# 1A_MAIN.net
KiCad netlist of a schematic drawn in EAGLE
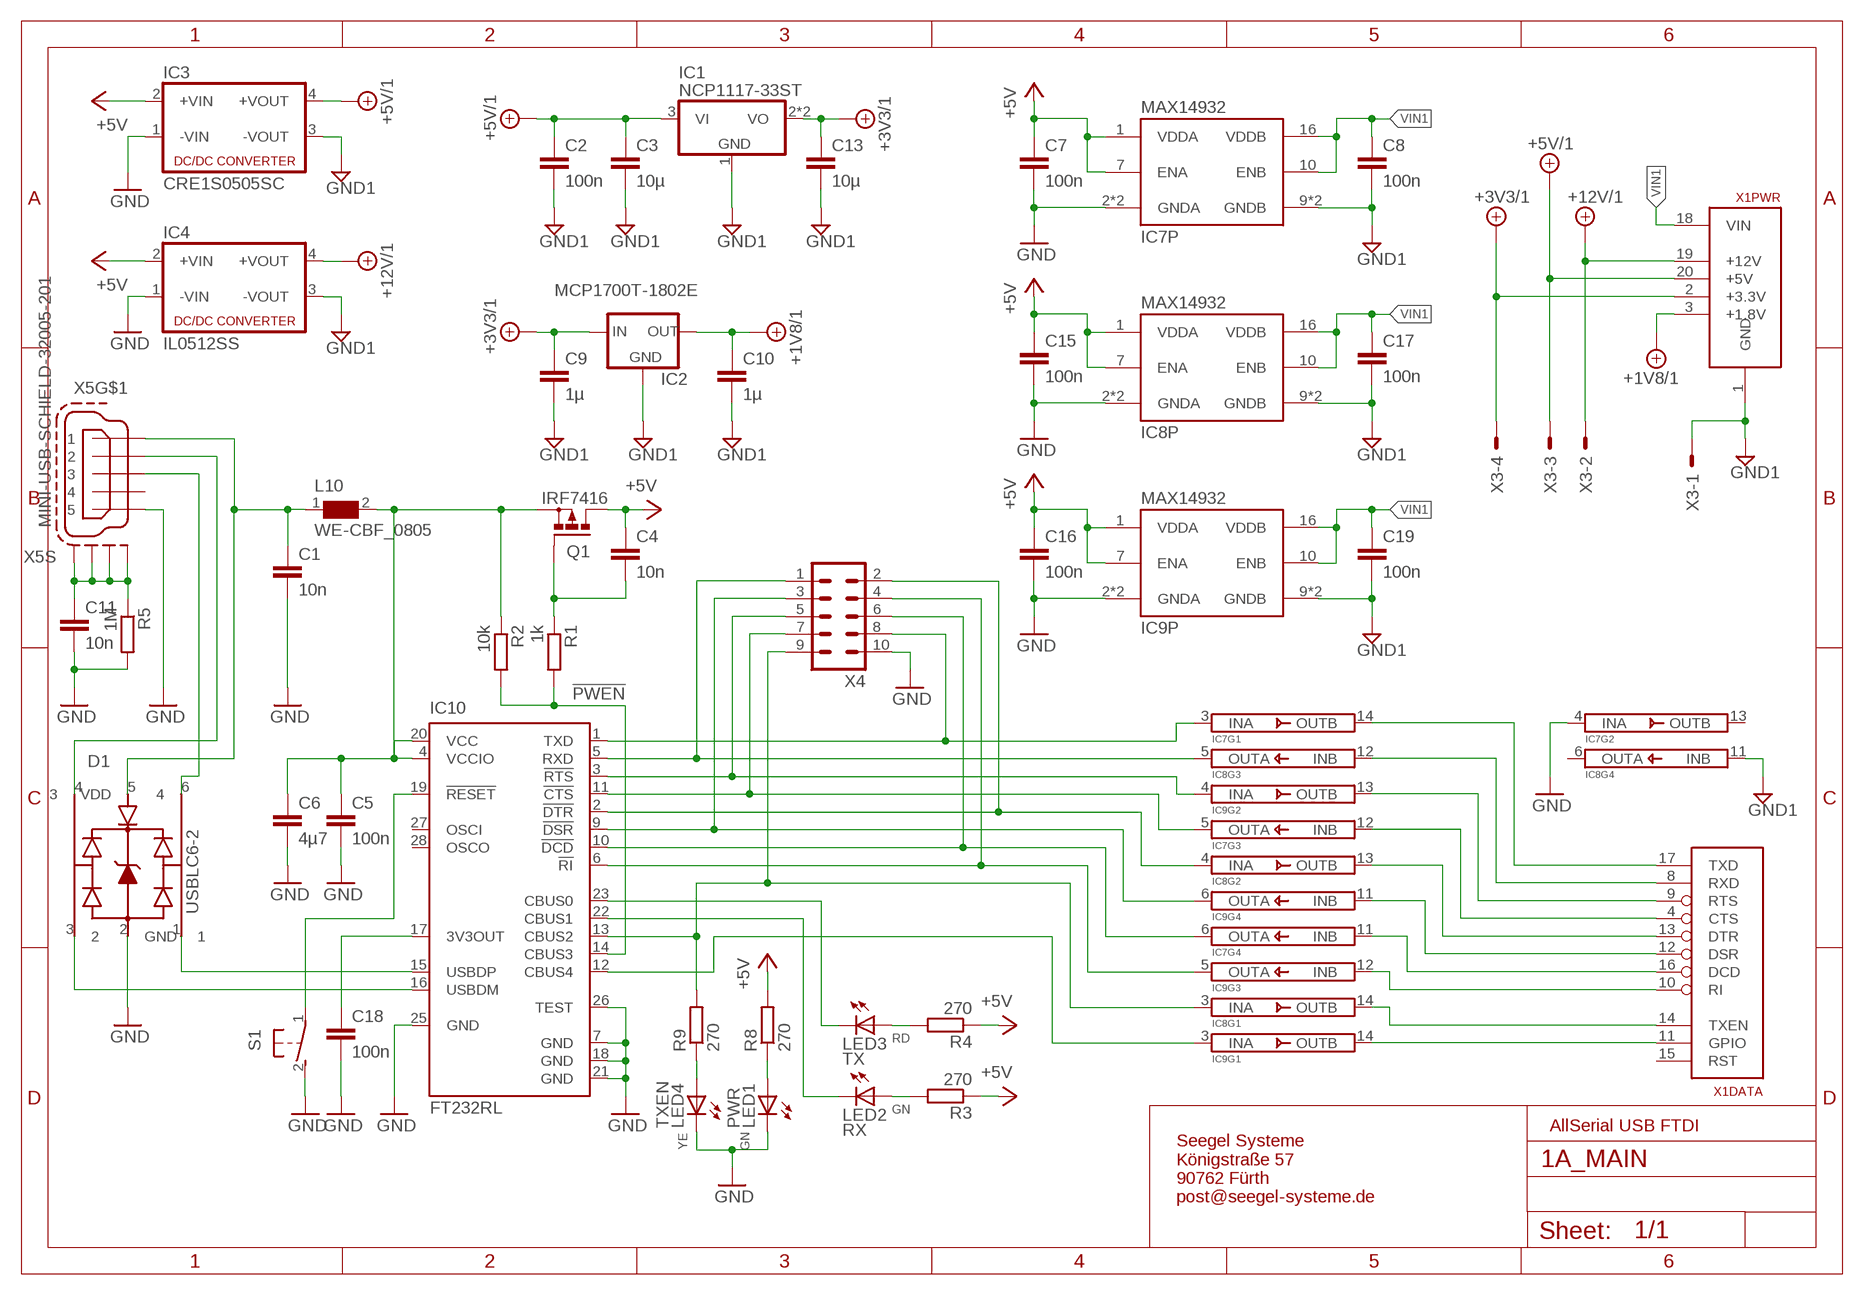
[diagram p0: schematic, sheet 1]

(export (version "E")
  (design (tool "Eeschema 10.0.6"))
  (components
    (comp (ref "C1")
      (value "10n")
      (footprint "eagle-import:C0805")
      (libsource (lib "eagle-import") (part "C-EUC0805"))
    )
    (comp (ref "C2")
      (value "100n")
      (footprint "eagle-import:C0805")
      (libsource (lib "eagle-import") (part "C-EUC0805"))
    )
    (comp (ref "C3")
      (value "10µ")
      (footprint "eagle-import:C0805")
      (libsource (lib "eagle-import") (part "C-EUC0805"))
    )
    (comp (ref "C4")
      (value "10n")
      (footprint "eagle-import:C0805")
      (libsource (lib "eagle-import") (part "C-EUC0805"))
    )
    (comp (ref "C5")
      (value "100n")
      (footprint "eagle-import:C0805")
      (libsource (lib "eagle-import") (part "C-EUC0805"))
    )
    (comp (ref "C6")
      (value "4µ7")
      (footprint "eagle-import:C0805")
      (libsource (lib "eagle-import") (part "C-EUC0805"))
    )
    (comp (ref "C7")
      (value "100n")
      (footprint "eagle-import:C0805")
      (libsource (lib "eagle-import") (part "C-EUC0805"))
    )
    (comp (ref "C8")
      (value "100n")
      (footprint "eagle-import:C0805")
      (libsource (lib "eagle-import") (part "C-EUC0805"))
    )
    (comp (ref "C9")
      (value "1µ")
      (footprint "eagle-import:C0805")
      (libsource (lib "eagle-import") (part "C-EUC0805"))
    )
    (comp (ref "C10")
      (value "1µ")
      (footprint "eagle-import:C0805")
      (libsource (lib "eagle-import") (part "C-EUC0805"))
    )
    (comp (ref "C11")
      (value "10n")
      (footprint "eagle-import:C0805")
      (libsource (lib "eagle-import") (part "C-EUC0805"))
    )
    (comp (ref "C13")
      (value "10µ")
      (footprint "eagle-import:C0805")
      (libsource (lib "eagle-import") (part "C-EUC0805"))
    )
    (comp (ref "C15")
      (value "100n")
      (footprint "eagle-import:C0805")
      (libsource (lib "eagle-import") (part "C-EUC0805"))
    )
    (comp (ref "C16")
      (value "100n")
      (footprint "eagle-import:C0805")
      (libsource (lib "eagle-import") (part "C-EUC0805"))
    )
    (comp (ref "C17")
      (value "100n")
      (footprint "eagle-import:C0805")
      (libsource (lib "eagle-import") (part "C-EUC0805"))
    )
    (comp (ref "C18")
      (value "100n")
      (footprint "eagle-import:C0805")
      (libsource (lib "eagle-import") (part "C-EUC0805"))
    )
    (comp (ref "C19")
      (value "100n")
      (footprint "eagle-import:C0805")
      (libsource (lib "eagle-import") (part "C-EUC0805"))
    )
    (comp (ref "D1")
      (value "USBLC6-2")
      (footprint "eagle-import:WE-TVS_SOT23-6L")
      (libsource (lib "eagle-import") (part "WE-TVS_82400102"))
    )
    (comp (ref "IC1")
      (value "NCP1117-33ST")
      (footprint "eagle-import:SOT223")
      (libsource (lib "eagle-import") (part "NCP1117ST-33"))
    )
    (comp (ref "IC2")
      (value "MCP1700T-1802E")
      (footprint "eagle-import:SOT23")
      (libsource (lib "eagle-import") (part "MCP170X"))
    )
    (comp (ref "IC3")
      (value "CRE1S0505SC")
      (footprint "eagle-import:MURATA-SC")
      (libsource (lib "eagle-import") (part "CRE1S?SC0505"))
    )
    (comp (ref "IC4")
      (value "IL0512SS")
      (footprint "eagle-import:XPPOWER-SIP")
      (libsource (lib "eagle-import") (part "ILSS0512"))
    )
    (comp (ref "IC7")
      (value "MAX14932")
      (footprint "eagle-import:SO16")
      (libsource (lib "eagle-import") (part "MAX14932"))
    )
    (comp (ref "IC8")
      (value "MAX14932")
      (footprint "eagle-import:SO16")
      (libsource (lib "eagle-import") (part "MAX14932"))
    )
    (comp (ref "IC9")
      (value "MAX14932")
      (footprint "eagle-import:SO16")
      (libsource (lib "eagle-import") (part "MAX14932"))
    )
    (comp (ref "IC10")
      (value "FT232RL")
      (footprint "eagle-import:SSOP28")
      (libsource (lib "eagle-import") (part "FT232RL"))
    )
    (comp (ref "L10")
      (value "WE-CBF_0805")
      (footprint "eagle-import:0805")
      (libsource (lib "eagle-import") (part "WE-CBF_0805"))
    )
    (comp (ref "LED1")
      (value "PWR")
      (footprint "eagle-import:CHIPLED_0603")
      (fields (field (name "COLOR") "GN"))
      (libsource (lib "eagle-import") (part "LEDCHIPLED_0603"))
    )
    (comp (ref "LED2")
      (value "RX")
      (footprint "eagle-import:CHIPLED_0603")
      (fields (field (name "COLOR") "GN"))
      (libsource (lib "eagle-import") (part "LEDCHIPLED_0603"))
    )
    (comp (ref "LED3")
      (value "TX")
      (footprint "eagle-import:CHIPLED_0603")
      (fields (field (name "COLOR") "RD"))
      (libsource (lib "eagle-import") (part "LEDCHIPLED_0603"))
    )
    (comp (ref "LED4")
      (value "TXEN")
      (footprint "eagle-import:CHIPLED_0603")
      (fields (field (name "COLOR") "YE"))
      (libsource (lib "eagle-import") (part "LEDCHIPLED_0603"))
    )
    (comp (ref "Q1")
      (value "IRF7416")
      (footprint "eagle-import:SO-08")
      (libsource (lib "eagle-import") (part "P-MOSFET-SO8"))
    )
    (comp (ref "R1")
      (value "1k")
      (footprint "eagle-import:R0805")
      (libsource (lib "eagle-import") (part "R-EU_R0805"))
    )
    (comp (ref "R2")
      (value "10k")
      (footprint "eagle-import:R0805")
      (libsource (lib "eagle-import") (part "R-EU_R0805"))
    )
    (comp (ref "R3")
      (value "270")
      (footprint "eagle-import:R0805")
      (libsource (lib "eagle-import") (part "R-EU_R0805"))
    )
    (comp (ref "R4")
      (value "270")
      (footprint "eagle-import:R0805")
      (libsource (lib "eagle-import") (part "R-EU_R0805"))
    )
    (comp (ref "R5")
      (value "1M")
      (footprint "eagle-import:R0805")
      (libsource (lib "eagle-import") (part "R-EU_R0805"))
    )
    (comp (ref "R8")
      (value "270")
      (footprint "eagle-import:R0805")
      (libsource (lib "eagle-import") (part "R-EU_R0805"))
    )
    (comp (ref "R9")
      (value "270")
      (footprint "eagle-import:R0805")
      (libsource (lib "eagle-import") (part "R-EU_R0805"))
    )
    (comp (ref "S1")
      (value "31-XX")
      (footprint "eagle-import:B3F-31XX")
      (fields (field (name "MPN") "B3F-3100"))
      (libsource (lib "eagle-import") (part "31-XX"))
    )
    (comp (ref "X1")
      (value "ALLSERIALMASTERMM")
      (footprint "eagle-import:MAIN-THT")
      (libsource (lib "eagle-import") (part "ALLSERIALMASTERMM"))
    )
    (comp (ref "X3")
      (value "AKL18X-04W")
      (footprint "eagle-import:AKL182-04")
      (libsource (lib "eagle-import") (part "AKL18X-04W"))
    )
    (comp (ref "X4")
      (value "ML10")
      (footprint "eagle-import:ML10")
      (libsource (lib "eagle-import") (part "ML10"))
    )
    (comp (ref "X5")
      (value "MINI-USB-SCHIELD-32005-201")
      (footprint "eagle-import:32005-201")
      (libsource (lib "eagle-import") (part "MINI-USB-SCHIELD-32005-201"))
    )
  )
  (nets
    (net (code "1") (name "+1V8{slash}1") (class "Default")
      (node (ref "C10") (pin "1") (pinfunction "1_1") (pintype "passive"))
      (node (ref "IC2") (pin "2") (pinfunction "OUT_2") (pintype "passive"))
      (node (ref "X1") (pin "3") (pinfunction "+1.8V_3") (pintype "bidirectional"))
    )
    (net (code "2") (name "+3V3{slash}1") (class "Default")
      (node (ref "C13") (pin "1") (pinfunction "1_1") (pintype "passive"))
      (node (ref "C9") (pin "1") (pinfunction "1_1") (pintype "passive"))
      (node (ref "IC1") (pin "2") (pinfunction "VO_2") (pintype "passive"))
      (node (ref "IC1") (pin "4") (pinfunction "VO_4") (pintype "passive"))
      (node (ref "IC2") (pin "3") (pinfunction "IN_3") (pintype "input"))
      (node (ref "X1") (pin "2") (pinfunction "+3.3V_2") (pintype "bidirectional"))
      (node (ref "X3") (pin "P$4") (pinfunction "S_P$4") (pintype "passive"))
    )
    (net (code "3") (name "+5V") (class "Default")
      (node (ref "C15") (pin "1") (pinfunction "1_1") (pintype "passive"))
      (node (ref "C16") (pin "1") (pinfunction "1_1") (pintype "passive"))
      (node (ref "C4") (pin "1") (pinfunction "1_1") (pintype "passive"))
      (node (ref "C7") (pin "1") (pinfunction "1_1") (pintype "passive"))
      (node (ref "IC3") (pin "2") (pinfunction "+VIN_2") (pintype "passive"))
      (node (ref "IC4") (pin "2") (pinfunction "+VIN_2") (pintype "passive"))
      (node (ref "IC7") (pin "1") (pinfunction "VDDA_1") (pintype "power_in"))
      (node (ref "IC7") (pin "7") (pinfunction "ENA_7") (pintype "input"))
      (node (ref "IC8") (pin "1") (pinfunction "VDDA_1") (pintype "power_in"))
      (node (ref "IC8") (pin "7") (pinfunction "ENA_7") (pintype "input"))
      (node (ref "IC9") (pin "1") (pinfunction "VDDA_1") (pintype "power_in"))
      (node (ref "IC9") (pin "7") (pinfunction "ENA_7") (pintype "input"))
      (node (ref "Q1") (pin "5") (pinfunction "D_5") (pintype "passive"))
      (node (ref "Q1") (pin "6") (pinfunction "D_6") (pintype "passive"))
      (node (ref "Q1") (pin "7") (pinfunction "D_7") (pintype "passive"))
      (node (ref "Q1") (pin "8") (pinfunction "D_8") (pintype "passive"))
      (node (ref "R3") (pin "1") (pinfunction "1_1") (pintype "passive"))
      (node (ref "R4") (pin "1") (pinfunction "1_1") (pintype "passive"))
      (node (ref "R8") (pin "2") (pinfunction "2_2") (pintype "passive"))
    )
    (net (code "4") (name "+5V{slash}1") (class "Default")
      (node (ref "C2") (pin "1") (pinfunction "1_1") (pintype "passive"))
      (node (ref "C3") (pin "1") (pinfunction "1_1") (pintype "passive"))
      (node (ref "IC1") (pin "3") (pinfunction "VI_3") (pintype "input"))
      (node (ref "IC3") (pin "4") (pinfunction "+VOUT_4") (pintype "passive"))
      (node (ref "X1") (pin "20") (pinfunction "+5V_20") (pintype "bidirectional"))
      (node (ref "X3") (pin "P$3") (pinfunction "S_P$3") (pintype "passive"))
    )
    (net (code "5") (name "+12V{slash}1") (class "Default")
      (node (ref "IC4") (pin "4") (pinfunction "+VOUT_4") (pintype "passive"))
      (node (ref "X1") (pin "19") (pinfunction "+12V_19") (pintype "bidirectional"))
      (node (ref "X3") (pin "P$2") (pinfunction "S_P$2") (pintype "passive"))
    )
    (net (code "6") (name "/~{PWEN}") (class "Default")
      (node (ref "IC10") (pin "14") (pinfunction "CBUS3_14") (pintype "bidirectional"))
      (node (ref "R1") (pin "2") (pinfunction "2_2") (pintype "passive"))
      (node (ref "R2") (pin "2") (pinfunction "2_2") (pintype "passive"))
    )
    (net (code "7") (name "GND") (class "Default")
      (node (ref "C1") (pin "2") (pinfunction "2_2") (pintype "passive"))
      (node (ref "C11") (pin "2") (pinfunction "2_2") (pintype "passive"))
      (node (ref "C15") (pin "2") (pinfunction "2_2") (pintype "passive"))
      (node (ref "C16") (pin "2") (pinfunction "2_2") (pintype "passive"))
      (node (ref "C18") (pin "2") (pinfunction "2_2") (pintype "passive"))
      (node (ref "C5") (pin "2") (pinfunction "2_2") (pintype "passive"))
      (node (ref "C6") (pin "2") (pinfunction "2_2") (pintype "passive"))
      (node (ref "C7") (pin "2") (pinfunction "2_2") (pintype "passive"))
      (node (ref "D1") (pin "2") (pinfunction "GND_2") (pintype "power_in"))
      (node (ref "IC10") (pin "18") (pinfunction "GND_18") (pintype "power_in"))
      (node (ref "IC10") (pin "21") (pinfunction "GND_21") (pintype "power_in"))
      (node (ref "IC10") (pin "25") (pinfunction "GND_25") (pintype "power_in"))
      (node (ref "IC10") (pin "26") (pinfunction "TEST_26") (pintype "input"))
      (node (ref "IC10") (pin "7") (pinfunction "GND_7") (pintype "power_in"))
      (node (ref "IC3") (pin "1") (pinfunction "-VIN_1") (pintype "passive"))
      (node (ref "IC4") (pin "1") (pinfunction "-VIN_1") (pintype "passive"))
      (node (ref "IC7") (pin "2") (pinfunction "GNDA_2") (pintype "power_in"))
      (node (ref "IC7") (pin "4") (pinfunction "INA_4") (pintype "input"))
      (node (ref "IC7") (pin "8") (pinfunction "GNDA_8") (pintype "power_in"))
      (node (ref "IC8") (pin "2") (pinfunction "GNDA_2") (pintype "power_in"))
      (node (ref "IC8") (pin "8") (pinfunction "GNDA_8") (pintype "power_in"))
      (node (ref "IC9") (pin "2") (pinfunction "GNDA_2") (pintype "power_in"))
      (node (ref "IC9") (pin "8") (pinfunction "GNDA_8") (pintype "power_in"))
      (node (ref "LED1") (pin "C") (pinfunction "C_C") (pintype "passive"))
      (node (ref "LED4") (pin "C") (pinfunction "C_C") (pintype "passive"))
      (node (ref "R5") (pin "2") (pinfunction "2_2") (pintype "passive"))
      (node (ref "S1") (pin "2") (pinfunction "S_2") (pintype "passive"))
      (node (ref "X4") (pin "10") (pinfunction "10_10") (pintype "passive"))
      (node (ref "X5") (pin "5") (pinfunction "5_5") (pintype "passive"))
    )
    (net (code "8") (name "GND1") (class "Default")
      (node (ref "C10") (pin "2") (pinfunction "2_2") (pintype "passive"))
      (node (ref "C13") (pin "2") (pinfunction "2_2") (pintype "passive"))
      (node (ref "C17") (pin "2") (pinfunction "2_2") (pintype "passive"))
      (node (ref "C19") (pin "2") (pinfunction "2_2") (pintype "passive"))
      (node (ref "C2") (pin "2") (pinfunction "2_2") (pintype "passive"))
      (node (ref "C3") (pin "2") (pinfunction "2_2") (pintype "passive"))
      (node (ref "C8") (pin "2") (pinfunction "2_2") (pintype "passive"))
      (node (ref "C9") (pin "2") (pinfunction "2_2") (pintype "passive"))
      (node (ref "IC1") (pin "1") (pinfunction "GND_1") (pintype "passive"))
      (node (ref "IC2") (pin "1") (pinfunction "GND_1") (pintype "input"))
      (node (ref "IC3") (pin "3") (pinfunction "-VOUT_3") (pintype "passive"))
      (node (ref "IC4") (pin "3") (pinfunction "-VOUT_3") (pintype "passive"))
      (node (ref "IC7") (pin "15") (pinfunction "GNDB_15") (pintype "power_in"))
      (node (ref "IC7") (pin "9") (pinfunction "GNDB_9") (pintype "power_in"))
      (node (ref "IC8") (pin "11") (pinfunction "INB_11") (pintype "input"))
      (node (ref "IC8") (pin "15") (pinfunction "GNDB_15") (pintype "power_in"))
      (node (ref "IC8") (pin "9") (pinfunction "GNDB_9") (pintype "power_in"))
      (node (ref "IC9") (pin "15") (pinfunction "GNDB_15") (pintype "power_in"))
      (node (ref "IC9") (pin "9") (pinfunction "GNDB_9") (pintype "power_in"))
      (node (ref "X1") (pin "1") (pinfunction "GND_1") (pintype "bidirectional"))
      (node (ref "X3") (pin "P$1") (pinfunction "S_P$1") (pintype "passive"))
    )
    (net (code "9") (name "Net-(D1-2)") (class "Default")
      (node (ref "D1") (pin "3") (pinfunction "2_3") (pintype "passive"))
      (node (ref "IC10") (pin "16") (pinfunction "USBDM_16") (pintype "bidirectional"))
    )
    (net (code "10") (name "Net-(D1-3)") (class "Default")
      (node (ref "D1") (pin "4") (pinfunction "3_4") (pintype "passive"))
      (node (ref "X5") (pin "2") (pinfunction "2_2") (pintype "passive"))
    )
    (net (code "11") (name "Net-(D1-4)") (class "Default")
      (node (ref "D1") (pin "6") (pinfunction "4_6") (pintype "passive"))
      (node (ref "X5") (pin "3") (pinfunction "3_3") (pintype "passive"))
    )
    (net (code "12") (name "Net-(D1-VDD)") (class "Default")
      (node (ref "C1") (pin "1") (pinfunction "1_1") (pintype "passive"))
      (node (ref "D1") (pin "5") (pinfunction "VDD_5") (pintype "power_in"))
      (node (ref "L10") (pin "1") (pinfunction "1_1") (pintype "passive"))
      (node (ref "X5") (pin "1") (pinfunction "1_1") (pintype "passive"))
    )
    (net (code "13") (name "Net-(IC7A-OUTB)") (class "Default")
      (node (ref "IC7") (pin "14") (pinfunction "OUTB_14") (pintype "output"))
      (node (ref "X1") (pin "17") (pinfunction "TXD_17") (pintype "input"))
    )
    (net (code "14") (name "Net-(IC7C-INB)") (class "Default")
      (node (ref "IC7") (pin "12") (pinfunction "INB_12") (pintype "input"))
      (node (ref "X1") (pin "4") (pinfunction "CTS_4") (pintype "output"))
    )
    (net (code "15") (name "Net-(IC7D-INB)") (class "Default")
      (node (ref "IC7") (pin "11") (pinfunction "INB_11") (pintype "input"))
      (node (ref "X1") (pin "16") (pinfunction "DCD_16") (pintype "output"))
    )
    (net (code "16") (name "Net-(IC8A-OUTB)") (class "Default")
      (node (ref "IC8") (pin "14") (pinfunction "OUTB_14") (pintype "output"))
      (node (ref "X1") (pin "14") (pinfunction "TXEN_14") (pintype "input"))
    )
    (net (code "17") (name "Net-(IC8B-OUTB)") (class "Default")
      (node (ref "IC8") (pin "13") (pinfunction "OUTB_13") (pintype "output"))
      (node (ref "X1") (pin "13") (pinfunction "DTR_13") (pintype "input"))
    )
    (net (code "18") (name "Net-(IC8C-INB)") (class "Default")
      (node (ref "IC8") (pin "12") (pinfunction "INB_12") (pintype "input"))
      (node (ref "X1") (pin "8") (pinfunction "RXD_8") (pintype "output"))
    )
    (net (code "19") (name "Net-(IC9A-OUTB)") (class "Default")
      (node (ref "IC9") (pin "14") (pinfunction "OUTB_14") (pintype "output"))
      (node (ref "X1") (pin "11") (pinfunction "GPIO_11") (pintype "bidirectional"))
    )
    (net (code "20") (name "Net-(IC9B-OUTB)") (class "Default")
      (node (ref "IC9") (pin "13") (pinfunction "OUTB_13") (pintype "output"))
      (node (ref "X1") (pin "9") (pinfunction "RTS_9") (pintype "input"))
    )
    (net (code "21") (name "Net-(IC9C-INB)") (class "Default")
      (node (ref "IC9") (pin "12") (pinfunction "INB_12") (pintype "input"))
      (node (ref "X1") (pin "10") (pinfunction "RI_10") (pintype "output"))
    )
    (net (code "22") (name "Net-(IC9D-INB)") (class "Default")
      (node (ref "IC9") (pin "11") (pinfunction "INB_11") (pintype "input"))
      (node (ref "X1") (pin "12") (pinfunction "DSR_12") (pintype "output"))
    )
    (net (code "23") (name "Net-(IC10-3V3OUT)") (class "Default")
      (node (ref "C18") (pin "1") (pinfunction "1_1") (pintype "passive"))
      (node (ref "IC10") (pin "17") (pinfunction "3V3OUT_17") (pintype "output"))
    )
    (net (code "24") (name "Net-(IC10-CBUS0)") (class "Default")
      (node (ref "IC10") (pin "23") (pinfunction "CBUS0_23") (pintype "bidirectional"))
      (node (ref "LED3") (pin "C") (pinfunction "C_C") (pintype "passive"))
    )
    (net (code "25") (name "Net-(IC10-CBUS1)") (class "Default")
      (node (ref "IC10") (pin "22") (pinfunction "CBUS1_22") (pintype "bidirectional"))
      (node (ref "LED2") (pin "C") (pinfunction "C_C") (pintype "passive"))
    )
    (net (code "26") (name "Net-(IC10-CBUS2)") (class "Default")
      (node (ref "IC10") (pin "13") (pinfunction "CBUS2_13") (pintype "bidirectional"))
      (node (ref "IC8") (pin "3") (pinfunction "INA_3") (pintype "input"))
      (node (ref "R9") (pin "2") (pinfunction "2_2") (pintype "passive"))
      (node (ref "X4") (pin "9") (pinfunction "9_9") (pintype "passive"))
    )
    (net (code "27") (name "Net-(IC10-CBUS4)") (class "Default")
      (node (ref "IC10") (pin "12") (pinfunction "CBUS4_12") (pintype "bidirectional"))
      (node (ref "IC9") (pin "3") (pinfunction "INA_3") (pintype "input"))
    )
    (net (code "28") (name "Net-(IC10-RXD)") (class "Default")
      (node (ref "IC10") (pin "5") (pinfunction "RXD_5") (pintype "input"))
      (node (ref "IC8") (pin "5") (pinfunction "OUTA_5") (pintype "output"))
      (node (ref "X4") (pin "1") (pinfunction "1_1") (pintype "passive"))
    )
    (net (code "29") (name "Net-(IC10-TXD)") (class "Default")
      (node (ref "IC10") (pin "1") (pinfunction "TXD_1") (pintype "output"))
      (node (ref "IC7") (pin "3") (pinfunction "INA_3") (pintype "input"))
      (node (ref "X4") (pin "8") (pinfunction "8_8") (pintype "passive"))
    )
    (net (code "30") (name "Net-(IC10-USBDP)") (class "Default")
      (node (ref "D1") (pin "1") (pinfunction "1_1") (pintype "passive"))
      (node (ref "IC10") (pin "15") (pinfunction "USBDP_15") (pintype "bidirectional"))
    )
    (net (code "31") (name "Net-(IC10-VCC)") (class "Default")
      (node (ref "C5") (pin "1") (pinfunction "1_1") (pintype "passive"))
      (node (ref "C6") (pin "1") (pinfunction "1_1") (pintype "passive"))
      (node (ref "IC10") (pin "20") (pinfunction "VCC_20") (pintype "power_in"))
      (node (ref "IC10") (pin "4") (pinfunction "VCCIO_4") (pintype "power_in"))
      (node (ref "L10") (pin "2") (pinfunction "2_2") (pintype "passive"))
      (node (ref "Q1") (pin "1") (pinfunction "S_1") (pintype "passive"))
      (node (ref "Q1") (pin "2") (pinfunction "S_2") (pintype "passive"))
      (node (ref "Q1") (pin "3") (pinfunction "S_3") (pintype "passive"))
      (node (ref "R2") (pin "1") (pinfunction "1_1") (pintype "passive"))
    )
    (net (code "32") (name "Net-(IC10-~{CTS})") (class "Default")
      (node (ref "IC10") (pin "11") (pinfunction "~{CTS}_11") (pintype "input"))
      (node (ref "IC7") (pin "5") (pinfunction "OUTA_5") (pintype "output"))
      (node (ref "X4") (pin "7") (pinfunction "7_7") (pintype "passive"))
    )
    (net (code "33") (name "Net-(IC10-~{DCD})") (class "Default")
      (node (ref "IC10") (pin "10") (pinfunction "~{DCD}_10") (pintype "input"))
      (node (ref "IC7") (pin "6") (pinfunction "OUTA_6") (pintype "output"))
      (node (ref "X4") (pin "6") (pinfunction "6_6") (pintype "passive"))
    )
    (net (code "34") (name "Net-(IC10-~{DSR})") (class "Default")
      (node (ref "IC10") (pin "9") (pinfunction "~{DSR}_9") (pintype "input"))
      (node (ref "IC9") (pin "6") (pinfunction "OUTA_6") (pintype "output"))
      (node (ref "X4") (pin "3") (pinfunction "3_3") (pintype "passive"))
    )
    (net (code "35") (name "Net-(IC10-~{DTR})") (class "Default")
      (node (ref "IC10") (pin "2") (pinfunction "~{DTR}_2") (pintype "output"))
      (node (ref "IC8") (pin "4") (pinfunction "INA_4") (pintype "input"))
      (node (ref "X4") (pin "2") (pinfunction "2_2") (pintype "passive"))
    )
    (net (code "36") (name "Net-(IC10-~{RESET})") (class "Default")
      (node (ref "IC10") (pin "19") (pinfunction "~{RESET}_19") (pintype "input"))
      (node (ref "S1") (pin "1") (pinfunction "P_1") (pintype "passive"))
    )
    (net (code "37") (name "Net-(IC10-~{RI})") (class "Default")
      (node (ref "IC10") (pin "6") (pinfunction "~{RI}_6") (pintype "input"))
      (node (ref "IC9") (pin "5") (pinfunction "OUTA_5") (pintype "output"))
      (node (ref "X4") (pin "4") (pinfunction "4_4") (pintype "passive"))
    )
    (net (code "38") (name "Net-(IC10-~{RTS})") (class "Default")
      (node (ref "IC10") (pin "3") (pinfunction "~{RTS}_3") (pintype "output"))
      (node (ref "IC9") (pin "4") (pinfunction "INA_4") (pintype "input"))
      (node (ref "X4") (pin "5") (pinfunction "5_5") (pintype "passive"))
    )
    (net (code "39") (name "Net-(LED1-PadA)") (class "Default")
      (node (ref "LED1") (pin "A") (pinfunction "A_A") (pintype "passive"))
      (node (ref "R8") (pin "1") (pinfunction "1_1") (pintype "passive"))
    )
    (net (code "40") (name "Net-(LED2-PadA)") (class "Default")
      (node (ref "LED2") (pin "A") (pinfunction "A_A") (pintype "passive"))
      (node (ref "R3") (pin "2") (pinfunction "2_2") (pintype "passive"))
    )
    (net (code "41") (name "Net-(LED3-PadA)") (class "Default")
      (node (ref "LED3") (pin "A") (pinfunction "A_A") (pintype "passive"))
      (node (ref "R4") (pin "2") (pinfunction "2_2") (pintype "passive"))
    )
    (net (code "42") (name "Net-(LED4-PadA)") (class "Default")
      (node (ref "LED4") (pin "A") (pinfunction "A_A") (pintype "passive"))
      (node (ref "R9") (pin "1") (pinfunction "1_1") (pintype "passive"))
    )
    (net (code "43") (name "Net-(Q1-G)") (class "Default")
      (node (ref "C4") (pin "2") (pinfunction "2_2") (pintype "passive"))
      (node (ref "Q1") (pin "4") (pinfunction "G_4") (pintype "passive"))
      (node (ref "R1") (pin "1") (pinfunction "1_1") (pintype "passive"))
    )
    (net (code "44") (name "Net-(X5B-S1)") (class "Default")
      (node (ref "C11") (pin "1") (pinfunction "1_1") (pintype "passive"))
      (node (ref "R5") (pin "1") (pinfunction "1_1") (pintype "passive"))
      (node (ref "X5") (pin "M1") (pinfunction "S1_M1") (pintype "passive"))
      (node (ref "X5") (pin "M2") (pinfunction "S2_M2") (pintype "passive"))
      (node (ref "X5") (pin "M3") (pinfunction "S3_M3") (pintype "passive"))
      (node (ref "X5") (pin "M4") (pinfunction "S4_M4") (pintype "passive"))
    )
    (net (code "45") (name "VIN1") (class "Default")
      (node (ref "C17") (pin "1") (pinfunction "1_1") (pintype "passive"))
      (node (ref "C19") (pin "1") (pinfunction "1_1") (pintype "passive"))
      (node (ref "C8") (pin "1") (pinfunction "1_1") (pintype "passive"))
      (node (ref "IC7") (pin "10") (pinfunction "ENB_10") (pintype "input"))
      (node (ref "IC7") (pin "16") (pinfunction "VDDB_16") (pintype "power_in"))
      (node (ref "IC8") (pin "10") (pinfunction "ENB_10") (pintype "input"))
      (node (ref "IC8") (pin "16") (pinfunction "VDDB_16") (pintype "power_in"))
      (node (ref "IC9") (pin "10") (pinfunction "ENB_10") (pintype "input"))
      (node (ref "IC9") (pin "16") (pinfunction "VDDB_16") (pintype "power_in"))
      (node (ref "X1") (pin "18") (pinfunction "VIN_18") (pintype "bidirectional"))
    )
    (net (code "46") (name "unconnected-(IC7B-OUTB-Pad13)") (class "Default")
      (node (ref "IC7") (pin "13") (pinfunction "OUTB_13") (pintype "output"))
    )
    (net (code "47") (name "unconnected-(IC8D-OUTA-Pad6)") (class "Default")
      (node (ref "IC8") (pin "6") (pinfunction "OUTA_6") (pintype "output"))
    )
    (net (code "48") (name "unconnected-(IC10-OSCI-Pad27)") (class "Default")
      (node (ref "IC10") (pin "27") (pinfunction "OSCI_27") (pintype "input"))
    )
    (net (code "49") (name "unconnected-(IC10-OSCO-Pad28)") (class "Default")
      (node (ref "IC10") (pin "28") (pinfunction "OSCO_28") (pintype "output"))
    )
    (net (code "50") (name "unconnected-(X1A-RST-Pad15)") (class "Default")
      (node (ref "X1") (pin "15") (pinfunction "RST_15") (pintype "bidirectional"))
    )
    (net (code "51") (name "unconnected-(X5-Pad4)") (class "Default")
      (node (ref "X5") (pin "4") (pinfunction "4_4") (pintype "passive"))
    )
  )
)
